# Practicum.net
KiCad netlist of a schematic drawn in EAGLE
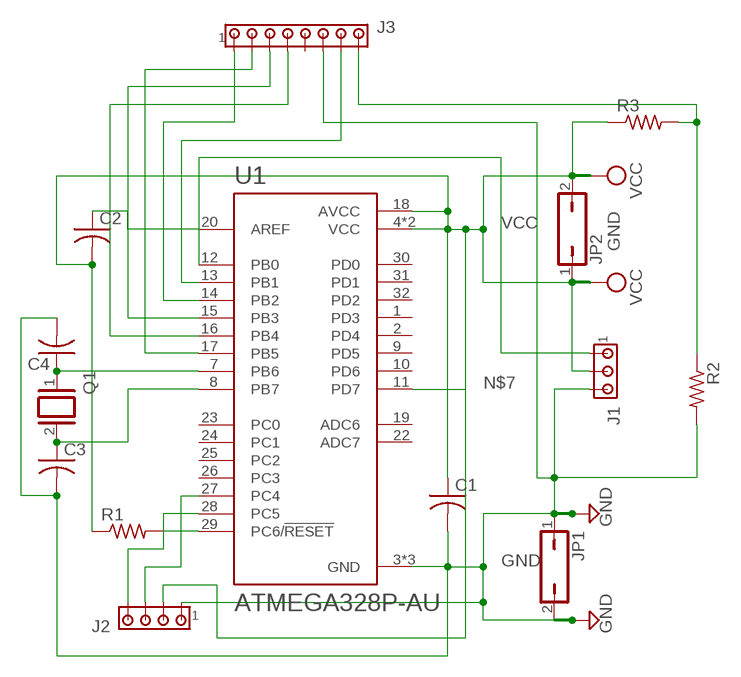
[diagram p0: schematic, sheet 1]

(export (version "E")
  (design (tool "Eeschema 10.0.6"))
  (components
    (comp (ref "C1")
      (value "C-USC0603")
      (footprint "eagle-import:C0603")
      (libsource (lib "eagle-import") (part "C-USC0603"))
    )
    (comp (ref "C2")
      (value "C-USC0603")
      (footprint "eagle-import:C0603")
      (libsource (lib "eagle-import") (part "C-USC0603"))
    )
    (comp (ref "C3")
      (value "C-USC0603")
      (footprint "eagle-import:C0603")
      (libsource (lib "eagle-import") (part "C-USC0603"))
    )
    (comp (ref "C4")
      (value "C-USC0603")
      (footprint "eagle-import:C0603")
      (libsource (lib "eagle-import") (part "C-USC0603"))
    )
    (comp (ref "J1")
      (value "MTA03-100")
      (footprint "eagle-import:10X03MTA")
      (libsource (lib "eagle-import") (part "MTA03-100"))
    )
    (comp (ref "J2")
      (value "MTA04-100")
      (footprint "eagle-import:10X04MTA")
      (libsource (lib "eagle-import") (part "MTA04-100"))
    )
    (comp (ref "J3")
      (value "MTA08-100")
      (footprint "eagle-import:10X08MTA")
      (libsource (lib "eagle-import") (part "MTA08-100"))
    )
    (comp (ref "JP1")
      (value "JP1Q")
      (footprint "eagle-import:JP1")
      (libsource (lib "eagle-import") (part "JP1Q"))
    )
    (comp (ref "JP2")
      (value "JP1Q")
      (footprint "eagle-import:JP1")
      (libsource (lib "eagle-import") (part "JP1Q"))
    )
    (comp (ref "Q1")
      (value "XTAL/S")
      (footprint "eagle-import:QS")
      (libsource (lib "eagle-import") (part "XTAL/S"))
    )
    (comp (ref "R1")
      (value "R-US_R0603")
      (footprint "eagle-import:R0603")
      (libsource (lib "eagle-import") (part "R-US_R0603"))
    )
    (comp (ref "R2")
      (value "R-US_R0603")
      (footprint "eagle-import:R0603")
      (libsource (lib "eagle-import") (part "R-US_R0603"))
    )
    (comp (ref "R3")
      (value "R-US_R0603")
      (footprint "eagle-import:R0603")
      (libsource (lib "eagle-import") (part "R-US_R0603"))
    )
    (comp (ref "U1")
      (value "ATMEGA328P-AU")
      (footprint "eagle-import:QFP80P900X900X120-32N")
      (fields (field (name "MF") "Microchip"))
      (libsource (lib "eagle-import") (part "ATMEGA328P-AU"))
    )
  )
  (nets
    (net (code "1") (name "/N$7") (class "Default")
      (node (ref "U1") (pin "11") (pinfunction "PD7_11") (pintype "bidirectional"))
    )
    (net (code "2") (name "GND") (class "Default")
      (node (ref "C1") (pin "2") (pinfunction "2_2") (pintype "passive"))
      (node (ref "C3") (pin "2") (pinfunction "2_2") (pintype "passive"))
      (node (ref "C4") (pin "2") (pinfunction "2_2") (pintype "passive"))
      (node (ref "J1") (pin "3") (pinfunction "3_3") (pintype "passive"))
      (node (ref "J2") (pin "1") (pinfunction "1_1") (pintype "passive"))
      (node (ref "J3") (pin "6") (pinfunction "6_6") (pintype "passive"))
      (node (ref "JP1") (pin "1") (pinfunction "1_1") (pintype "passive"))
      (node (ref "JP1") (pin "2") (pinfunction "2_2") (pintype "passive"))
      (node (ref "R2") (pin "2") (pinfunction "2_2") (pintype "passive"))
      (node (ref "U1") (pin "21") (pinfunction "GND_21") (pintype "power_in"))
      (node (ref "U1") (pin "3") (pinfunction "GND_3") (pintype "power_in"))
      (node (ref "U1") (pin "5") (pinfunction "GND_5") (pintype "power_in"))
    )
    (net (code "3") (name "Net-(J3-Pad8)") (class "Default")
      (node (ref "J3") (pin "8") (pinfunction "8_8") (pintype "passive"))
      (node (ref "R2") (pin "1") (pinfunction "1_1") (pintype "passive"))
      (node (ref "R3") (pin "2") (pinfunction "2_2") (pintype "passive"))
    )
    (net (code "4") (name "Net-(U1-AREF)") (class "Default")
      (node (ref "C2") (pin "1") (pinfunction "1_1") (pintype "passive"))
      (node (ref "U1") (pin "20") (pinfunction "AREF_20") (pintype "input"))
    )
    (net (code "5") (name "Net-(U1-PB0)") (class "Default")
      (node (ref "J1") (pin "1") (pinfunction "1_1") (pintype "passive"))
      (node (ref "U1") (pin "12") (pinfunction "PB0_12") (pintype "bidirectional"))
    )
    (net (code "6") (name "Net-(U1-PB1)") (class "Default")
      (node (ref "J3") (pin "7") (pinfunction "7_7") (pintype "passive"))
      (node (ref "U1") (pin "13") (pinfunction "PB1_13") (pintype "bidirectional"))
    )
    (net (code "7") (name "Net-(U1-PB2)") (class "Default")
      (node (ref "J3") (pin "1") (pinfunction "1_1") (pintype "passive"))
      (node (ref "U1") (pin "14") (pinfunction "PB2_14") (pintype "bidirectional"))
    )
    (net (code "8") (name "Net-(U1-PB3)") (class "Default")
      (node (ref "J3") (pin "3") (pinfunction "3_3") (pintype "passive"))
      (node (ref "U1") (pin "15") (pinfunction "PB3_15") (pintype "bidirectional"))
    )
    (net (code "9") (name "Net-(U1-PB4)") (class "Default")
      (node (ref "J3") (pin "4") (pinfunction "4_4") (pintype "passive"))
      (node (ref "U1") (pin "16") (pinfunction "PB4_16") (pintype "bidirectional"))
    )
    (net (code "10") (name "Net-(U1-PB5)") (class "Default")
      (node (ref "J3") (pin "2") (pinfunction "2_2") (pintype "passive"))
      (node (ref "U1") (pin "17") (pinfunction "PB5_17") (pintype "bidirectional"))
    )
    (net (code "11") (name "Net-(U1-PB6)") (class "Default")
      (node (ref "C4") (pin "1") (pinfunction "1_1") (pintype "passive"))
      (node (ref "Q1") (pin "1") (pinfunction "1_1") (pintype "passive"))
      (node (ref "U1") (pin "7") (pinfunction "PB6_7") (pintype "bidirectional"))
    )
    (net (code "12") (name "Net-(U1-PB7)") (class "Default")
      (node (ref "C3") (pin "1") (pinfunction "1_1") (pintype "passive"))
      (node (ref "Q1") (pin "2") (pinfunction "2_2") (pintype "passive"))
      (node (ref "U1") (pin "8") (pinfunction "PB7_8") (pintype "bidirectional"))
    )
    (net (code "13") (name "Net-(U1-PC4)") (class "Default")
      (node (ref "J2") (pin "3") (pinfunction "3_3") (pintype "passive"))
      (node (ref "U1") (pin "27") (pinfunction "PC4_27") (pintype "bidirectional"))
    )
    (net (code "14") (name "Net-(U1-PC5)") (class "Default")
      (node (ref "J2") (pin "4") (pinfunction "4_4") (pintype "passive"))
      (node (ref "U1") (pin "28") (pinfunction "PC5_28") (pintype "bidirectional"))
    )
    (net (code "15") (name "Net-(U1-PC6{slash}~{RESET})") (class "Default")
      (node (ref "R1") (pin "2") (pinfunction "2_2") (pintype "passive"))
      (node (ref "U1") (pin "29") (pinfunction "PC6/~{RESET}_29") (pintype "bidirectional"))
    )
    (net (code "16") (name "VCC") (class "Default")
      (node (ref "C1") (pin "1") (pinfunction "1_1") (pintype "passive"))
      (node (ref "C2") (pin "2") (pinfunction "2_2") (pintype "passive"))
      (node (ref "J1") (pin "2") (pinfunction "2_2") (pintype "passive"))
      (node (ref "J2") (pin "2") (pinfunction "2_2") (pintype "passive"))
      (node (ref "JP2") (pin "1") (pinfunction "1_1") (pintype "passive"))
      (node (ref "JP2") (pin "2") (pinfunction "2_2") (pintype "passive"))
      (node (ref "R1") (pin "1") (pinfunction "1_1") (pintype "passive"))
      (node (ref "R3") (pin "1") (pinfunction "1_1") (pintype "passive"))
      (node (ref "U1") (pin "18") (pinfunction "AVCC_18") (pintype "power_in"))
      (node (ref "U1") (pin "4") (pinfunction "VCC_4") (pintype "power_in"))
      (node (ref "U1") (pin "6") (pinfunction "VCC_6") (pintype "power_in"))
    )
    (net (code "17") (name "unconnected-(J3-Pad5)") (class "Default")
      (node (ref "J3") (pin "5") (pinfunction "5_5") (pintype "passive"))
    )
    (net (code "18") (name "unconnected-(U1-ADC6-Pad19)") (class "Default")
      (node (ref "U1") (pin "19") (pinfunction "ADC6_19") (pintype "bidirectional"))
    )
    (net (code "19") (name "unconnected-(U1-ADC7-Pad22)") (class "Default")
      (node (ref "U1") (pin "22") (pinfunction "ADC7_22") (pintype "bidirectional"))
    )
    (net (code "20") (name "unconnected-(U1-PC0-Pad23)") (class "Default")
      (node (ref "U1") (pin "23") (pinfunction "PC0_23") (pintype "bidirectional"))
    )
    (net (code "21") (name "unconnected-(U1-PC1-Pad24)") (class "Default")
      (node (ref "U1") (pin "24") (pinfunction "PC1_24") (pintype "bidirectional"))
    )
    (net (code "22") (name "unconnected-(U1-PC2-Pad25)") (class "Default")
      (node (ref "U1") (pin "25") (pinfunction "PC2_25") (pintype "bidirectional"))
    )
    (net (code "23") (name "unconnected-(U1-PC3-Pad26)") (class "Default")
      (node (ref "U1") (pin "26") (pinfunction "PC3_26") (pintype "bidirectional"))
    )
    (net (code "24") (name "unconnected-(U1-PD0-Pad30)") (class "Default")
      (node (ref "U1") (pin "30") (pinfunction "PD0_30") (pintype "bidirectional"))
    )
    (net (code "25") (name "unconnected-(U1-PD1-Pad31)") (class "Default")
      (node (ref "U1") (pin "31") (pinfunction "PD1_31") (pintype "bidirectional"))
    )
    (net (code "26") (name "unconnected-(U1-PD2-Pad32)") (class "Default")
      (node (ref "U1") (pin "32") (pinfunction "PD2_32") (pintype "bidirectional"))
    )
    (net (code "27") (name "unconnected-(U1-PD3-Pad1)") (class "Default")
      (node (ref "U1") (pin "1") (pinfunction "PD3_1") (pintype "bidirectional"))
    )
    (net (code "28") (name "unconnected-(U1-PD4-Pad2)") (class "Default")
      (node (ref "U1") (pin "2") (pinfunction "PD4_2") (pintype "bidirectional"))
    )
    (net (code "29") (name "unconnected-(U1-PD5-Pad9)") (class "Default")
      (node (ref "U1") (pin "9") (pinfunction "PD5_9") (pintype "bidirectional"))
    )
    (net (code "30") (name "unconnected-(U1-PD6-Pad10)") (class "Default")
      (node (ref "U1") (pin "10") (pinfunction "PD6_10") (pintype "bidirectional"))
    )
  )
)
